# porcupine4v1_10.net
KiCad netlist of a schematic drawn in EAGLE
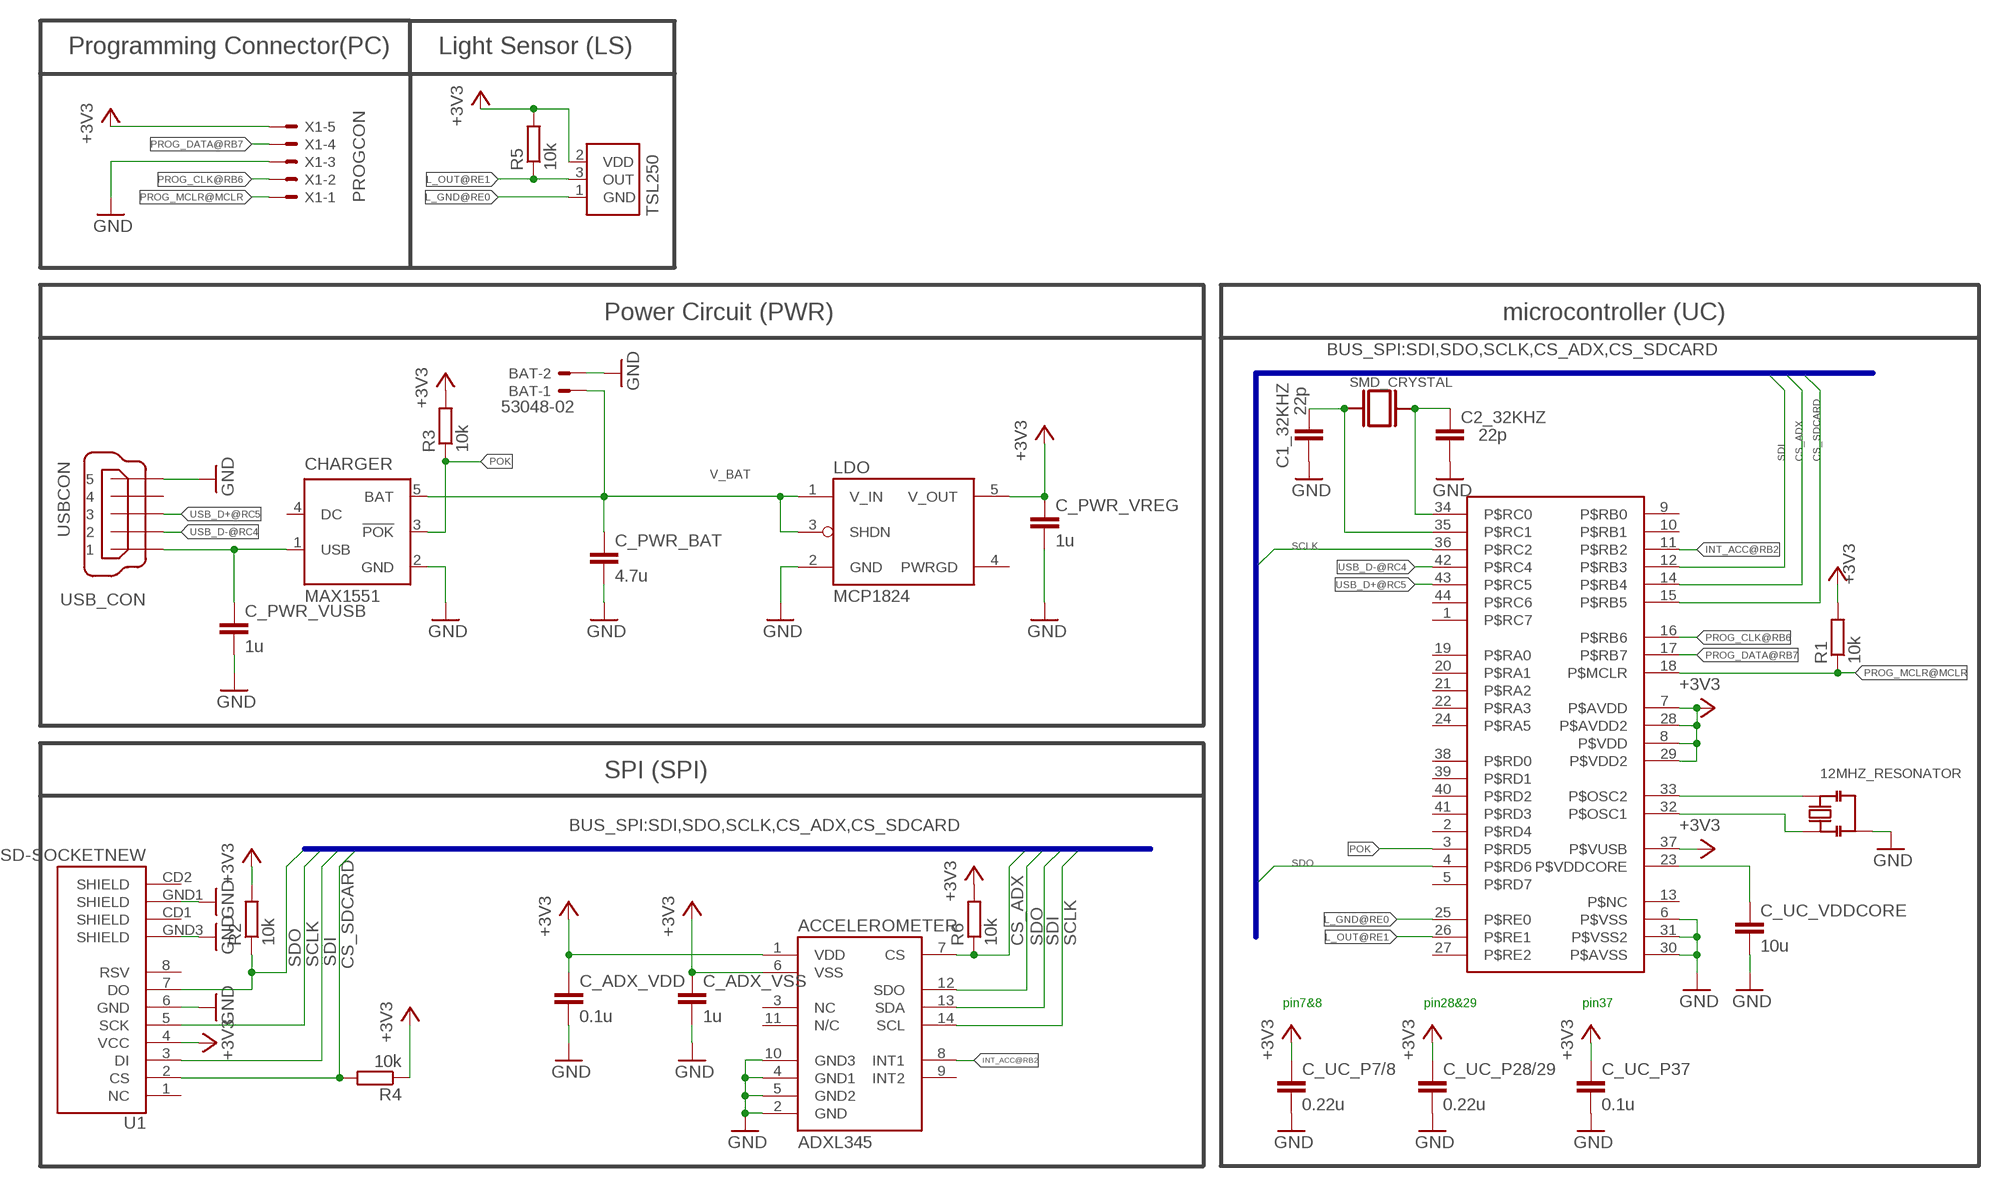
[diagram p0: schematic, sheet 1]

(export (version "E")
  (design (tool "Eeschema 10.0.6"))
  (components
    (comp (ref "12MHZ_RESONATOR")
      (value "RESONATORPRQC-C")
      (footprint "eagle-import:PRQC-C")
      (libsource (lib "eagle-import") (part "RESONATORPRQC-C"))
    )
    (comp (ref "32KHZ_CRYSTAL")
      (value "SMD_CRYSTAL")
      (footprint "eagle-import:SMD_CRYSTAL")
      (libsource (lib "eagle-import") (part "SMD_CRYSTAL"))
    )
    (comp (ref "ACCELEROMETER")
      (value "ADXL345")
      (footprint "eagle-import:LGA14")
      (libsource (lib "eagle-import") (part "ADXL345"))
    )
    (comp (ref "BAT")
      (value "53048-02")
      (footprint "eagle-import:53048-02")
      (fields (field (name "MF") "MOLEX") (field (name "MPN") "53048-0210"))
      (libsource (lib "eagle-import") (part "53?-02048"))
    )
    (comp (ref "C1_32KHZ")
      (value "22p")
      (footprint "eagle-import:C0603K")
      (libsource (lib "eagle-import") (part "C-EUC0603K"))
    )
    (comp (ref "C2_32KHZ")
      (value "22p")
      (footprint "eagle-import:C0603K")
      (libsource (lib "eagle-import") (part "C-EUC0603K"))
    )
    (comp (ref "CHARGER")
      (value "MAX1551")
      (footprint "eagle-import:SOT23-5L")
      (fields (field (name "MF") "MAXIM") (field (name "MPN") "MAX1551EZK-T"))
      (libsource (lib "eagle-import") (part "MAX1551"))
    )
    (comp (ref "C_ADX_VDD")
      (value "0.1u")
      (footprint "eagle-import:C0603K")
      (libsource (lib "eagle-import") (part "C-EUC0603K"))
    )
    (comp (ref "C_ADX_VSS")
      (value "1u")
      (footprint "eagle-import:C0603K")
      (libsource (lib "eagle-import") (part "C-EUC0603K"))
    )
    (comp (ref "C_PWR_BAT")
      (value "4.7u")
      (footprint "eagle-import:C0603K")
      (libsource (lib "eagle-import") (part "C-EUC0603K"))
    )
    (comp (ref "C_PWR_VREG")
      (value "1u")
      (footprint "eagle-import:C0603K")
      (libsource (lib "eagle-import") (part "C-EUC0603K"))
    )
    (comp (ref "C_PWR_VUSB")
      (value "1u")
      (footprint "eagle-import:C0603K")
      (libsource (lib "eagle-import") (part "C-EUC0603K"))
    )
    (comp (ref "C_UC_P7/8")
      (value "0.22u")
      (footprint "eagle-import:C0603K")
      (libsource (lib "eagle-import") (part "C-EUC0603K"))
    )
    (comp (ref "C_UC_P28/29")
      (value "0.22u")
      (footprint "eagle-import:C0603K")
      (libsource (lib "eagle-import") (part "C-EUC0603K"))
    )
    (comp (ref "C_UC_P37")
      (value "0.1u")
      (footprint "eagle-import:C0603K")
      (libsource (lib "eagle-import") (part "C-EUC0603K"))
    )
    (comp (ref "C_UC_VDDCORE")
      (value "10u")
      (footprint "eagle-import:C0805K")
      (libsource (lib "eagle-import") (part "C-EUC0805K"))
    )
    (comp (ref "LDO")
      (value "MCP1824")
      (footprint "eagle-import:SOT-23-5")
      (libsource (lib "eagle-import") (part "MCP1824"))
    )
    (comp (ref "LIGHTSENSE")
      (value "TSL250")
      (footprint "eagle-import:TSL")
      (libsource (lib "eagle-import") (part "TSL250"))
    )
    (comp (ref "PIC_CONTROLLER")
      (value "PIC_P2V6")
      (footprint "eagle-import:QFN44ML8X8")
      (libsource (lib "eagle-import") (part "PIC_P2V6"))
    )
    (comp (ref "R1")
      (value "10k")
      (footprint "eagle-import:R0603")
      (libsource (lib "eagle-import") (part "R-EU_R0603"))
    )
    (comp (ref "R2")
      (value "10k")
      (footprint "eagle-import:R0603")
      (libsource (lib "eagle-import") (part "R-EU_R0603"))
    )
    (comp (ref "R3")
      (value "10k")
      (footprint "eagle-import:R0603")
      (libsource (lib "eagle-import") (part "R-EU_R0603"))
    )
    (comp (ref "R4")
      (value "10k")
      (footprint "eagle-import:R0603")
      (libsource (lib "eagle-import") (part "R-EU_R0603"))
    )
    (comp (ref "R5")
      (value "10k")
      (footprint "eagle-import:R0603")
      (libsource (lib "eagle-import") (part "R-EU_R0603"))
    )
    (comp (ref "R6")
      (value "10k")
      (footprint "eagle-import:R0603")
      (libsource (lib "eagle-import") (part "R-EU_R0603"))
    )
    (comp (ref "U1")
      (value "USD-SOCKETNEW")
      (footprint "eagle-import:MICRO-SD-SOCKET-PP")
      (libsource (lib "eagle-import") (part "USD-SOCKETNEW"))
    )
    (comp (ref "USB_CON")
      (value "USBCON")
      (footprint "eagle-import:248601")
      (libsource (lib "eagle-import") (part "USBCON"))
    )
    (comp (ref "X1")
      (value "PROGCON")
      (footprint "eagle-import:53047-05-OCT")
      (libsource (lib "eagle-import") (part "PROGCON"))
    )
  )
  (nets
    (net (code "2") (name "+3V3") (class "Default")
      (node (ref "ACCELEROMETER") (pin "1") (pinfunction "VDD_1") (pintype "bidirectional"))
      (node (ref "ACCELEROMETER") (pin "6") (pinfunction "VSS_6") (pintype "bidirectional"))
      (node (ref "C_ADX_VDD") (pin "1") (pinfunction "1_1") (pintype "passive"))
      (node (ref "C_ADX_VSS") (pin "1") (pinfunction "1_1") (pintype "passive"))
      (node (ref "C_PWR_VREG") (pin "1") (pinfunction "1_1") (pintype "passive"))
      (node (ref "C_UC_P28/29") (pin "1") (pinfunction "1_1") (pintype "passive"))
      (node (ref "C_UC_P37") (pin "1") (pinfunction "1_1") (pintype "passive"))
      (node (ref "C_UC_P7/8") (pin "1") (pinfunction "1_1") (pintype "passive"))
      (node (ref "LDO") (pin "5") (pinfunction "V_OUT_5") (pintype "bidirectional"))
      (node (ref "LIGHTSENSE") (pin "2") (pinfunction "VDD_2") (pintype "power_in"))
      (node (ref "PIC_CONTROLLER") (pin "28") (pinfunction "P$AVDD2_28") (pintype "bidirectional"))
      (node (ref "PIC_CONTROLLER") (pin "29") (pinfunction "P$VDD2_29") (pintype "bidirectional"))
      (node (ref "PIC_CONTROLLER") (pin "37") (pinfunction "P$VUSB_37") (pintype "bidirectional"))
      (node (ref "PIC_CONTROLLER") (pin "7") (pinfunction "P$AVDD_7") (pintype "input"))
      (node (ref "PIC_CONTROLLER") (pin "8") (pinfunction "P$VDD_8") (pintype "bidirectional"))
      (node (ref "R1") (pin "2") (pinfunction "2_2") (pintype "passive"))
      (node (ref "R2") (pin "2") (pinfunction "2_2") (pintype "passive"))
      (node (ref "R3") (pin "2") (pinfunction "2_2") (pintype "passive"))
      (node (ref "R4") (pin "1") (pinfunction "1_1") (pintype "passive"))
      (node (ref "R5") (pin "2") (pinfunction "2_2") (pintype "passive"))
      (node (ref "R6") (pin "2") (pinfunction "2_2") (pintype "passive"))
      (node (ref "U1") (pin "4") (pinfunction "VCC_4") (pintype "bidirectional"))
      (node (ref "X1") (pin "5") (pinfunction "S_5") (pintype "passive"))
    )
    (net (code "3") (name "/CS_ADX") (class "Default")
      (node (ref "ACCELEROMETER") (pin "7") (pinfunction "CS_7") (pintype "bidirectional"))
      (node (ref "PIC_CONTROLLER") (pin "14") (pinfunction "P$RB4_14") (pintype "bidirectional"))
      (node (ref "R6") (pin "1") (pinfunction "1_1") (pintype "passive"))
    )
    (net (code "4") (name "/CS_SDCARD") (class "Default")
      (node (ref "PIC_CONTROLLER") (pin "15") (pinfunction "P$RB5_15") (pintype "bidirectional"))
      (node (ref "R4") (pin "2") (pinfunction "2_2") (pintype "passive"))
      (node (ref "U1") (pin "2") (pinfunction "CS_2") (pintype "bidirectional"))
    )
    (net (code "5") (name "/P$RD7") (class "Default")
      (node (ref "PIC_CONTROLLER") (pin "5") (pinfunction "P$RD7_5") (pintype "power_in"))
    )
    (net (code "6") (name "/SCLK") (class "Default")
      (node (ref "ACCELEROMETER") (pin "14") (pinfunction "SCL_14") (pintype "bidirectional"))
      (node (ref "PIC_CONTROLLER") (pin "36") (pinfunction "P$RC2_36") (pintype "bidirectional"))
      (node (ref "U1") (pin "5") (pinfunction "SCK_5") (pintype "bidirectional"))
    )
    (net (code "7") (name "/SDI") (class "Default")
      (node (ref "ACCELEROMETER") (pin "13") (pinfunction "SDA_13") (pintype "bidirectional"))
      (node (ref "PIC_CONTROLLER") (pin "12") (pinfunction "P$RB3_12") (pintype "bidirectional"))
      (node (ref "U1") (pin "3") (pinfunction "DI_3") (pintype "bidirectional"))
    )
    (net (code "8") (name "/SDO") (class "Default")
      (node (ref "ACCELEROMETER") (pin "12") (pinfunction "SDO_12") (pintype "bidirectional"))
      (node (ref "PIC_CONTROLLER") (pin "4") (pinfunction "P$RD6_4") (pintype "bidirectional"))
      (node (ref "R2") (pin "1") (pinfunction "1_1") (pintype "passive"))
      (node (ref "U1") (pin "7") (pinfunction "DO_7") (pintype "bidirectional"))
    )
    (net (code "9") (name "/V_BAT") (class "Default")
      (node (ref "BAT") (pin "1") (pinfunction "S_1") (pintype "passive"))
      (node (ref "CHARGER") (pin "5") (pinfunction "BAT_5") (pintype "passive"))
      (node (ref "C_PWR_BAT") (pin "1") (pinfunction "1_1") (pintype "passive"))
      (node (ref "LDO") (pin "1") (pinfunction "V_IN_1") (pintype "bidirectional"))
      (node (ref "LDO") (pin "3") (pinfunction "SHDN_3") (pintype "bidirectional"))
    )
    (net (code "11") (name "GND") (class "Default")
      (node (ref "12MHZ_RESONATOR") (pin "2_GND") (pinfunction "GND_2_GND") (pintype "bidirectional"))
      (node (ref "ACCELEROMETER") (pin "10") (pinfunction "GND3_10") (pintype "bidirectional"))
      (node (ref "ACCELEROMETER") (pin "2") (pinfunction "GND_2") (pintype "bidirectional"))
      (node (ref "ACCELEROMETER") (pin "4") (pinfunction "GND1_4") (pintype "bidirectional"))
      (node (ref "ACCELEROMETER") (pin "5") (pinfunction "GND2_5") (pintype "bidirectional"))
      (node (ref "BAT") (pin "2") (pinfunction "S_2") (pintype "passive"))
      (node (ref "C1_32KHZ") (pin "2") (pinfunction "2_2") (pintype "passive"))
      (node (ref "C2_32KHZ") (pin "2") (pinfunction "2_2") (pintype "passive"))
      (node (ref "CHARGER") (pin "2") (pinfunction "GND_2") (pintype "power_in"))
      (node (ref "C_ADX_VDD") (pin "2") (pinfunction "2_2") (pintype "passive"))
      (node (ref "C_ADX_VSS") (pin "2") (pinfunction "2_2") (pintype "passive"))
      (node (ref "C_PWR_BAT") (pin "2") (pinfunction "2_2") (pintype "passive"))
      (node (ref "C_PWR_VREG") (pin "2") (pinfunction "2_2") (pintype "passive"))
      (node (ref "C_PWR_VUSB") (pin "2") (pinfunction "2_2") (pintype "passive"))
      (node (ref "C_UC_P28/29") (pin "2") (pinfunction "2_2") (pintype "passive"))
      (node (ref "C_UC_P37") (pin "2") (pinfunction "2_2") (pintype "passive"))
      (node (ref "C_UC_P7/8") (pin "2") (pinfunction "2_2") (pintype "passive"))
      (node (ref "C_UC_VDDCORE") (pin "2") (pinfunction "2_2") (pintype "passive"))
      (node (ref "LDO") (pin "2") (pinfunction "GND_2") (pintype "bidirectional"))
      (node (ref "PIC_CONTROLLER") (pin "30") (pinfunction "P$AVSS_30") (pintype "input"))
      (node (ref "PIC_CONTROLLER") (pin "31") (pinfunction "P$VSS2_31") (pintype "output"))
      (node (ref "PIC_CONTROLLER") (pin "6") (pinfunction "P$VSS_6") (pintype "input"))
      (node (ref "U1") (pin "6") (pinfunction "GND_6") (pintype "bidirectional"))
      (node (ref "U1") (pin "GND1") (pinfunction "SHIELD_GND1") (pintype "bidirectional"))
      (node (ref "U1") (pin "GND3") (pinfunction "SHIELD_GND3") (pintype "bidirectional"))
      (node (ref "USB_CON") (pin "5") (pinfunction "5_5") (pintype "input"))
      (node (ref "X1") (pin "3") (pinfunction "S_3") (pintype "passive"))
    )
    (net (code "12") (name "INT_ACC@RB2") (class "Default")
      (node (ref "ACCELEROMETER") (pin "8") (pinfunction "INT1_8") (pintype "bidirectional"))
      (node (ref "PIC_CONTROLLER") (pin "11") (pinfunction "P$RB2_11") (pintype "power_in"))
    )
    (net (code "13") (name "L_GND@RE0") (class "Default")
      (node (ref "LIGHTSENSE") (pin "1") (pinfunction "GND_1") (pintype "power_in"))
      (node (ref "PIC_CONTROLLER") (pin "25") (pinfunction "P$RE0_25") (pintype "bidirectional"))
    )
    (net (code "14") (name "L_OUT@RE1") (class "Default")
      (node (ref "LIGHTSENSE") (pin "3") (pinfunction "OUT_3") (pintype "output"))
      (node (ref "PIC_CONTROLLER") (pin "26") (pinfunction "P$RE1_26") (pintype "input"))
      (node (ref "R5") (pin "1") (pinfunction "1_1") (pintype "passive"))
    )
    (net (code "15") (name "Net-(12MHZ_RESONATOR-2)") (class "Default")
      (node (ref "12MHZ_RESONATOR") (pin "3") (pinfunction "2_3") (pintype "bidirectional"))
      (node (ref "PIC_CONTROLLER") (pin "32") (pinfunction "P$OSC1_32") (pintype "bidirectional"))
    )
    (net (code "16") (name "Net-(32KHZ_CRYSTAL-1)") (class "Default")
      (node (ref "32KHZ_CRYSTAL") (pin "P$1") (pinfunction "1_P$1") (pintype "passive"))
      (node (ref "C1_32KHZ") (pin "1") (pinfunction "1_1") (pintype "passive"))
      (node (ref "PIC_CONTROLLER") (pin "35") (pinfunction "P$RC1_35") (pintype "bidirectional"))
    )
    (net (code "17") (name "Net-(32KHZ_CRYSTAL-2)") (class "Default")
      (node (ref "32KHZ_CRYSTAL") (pin "P$2") (pinfunction "2_P$2") (pintype "passive"))
      (node (ref "C2_32KHZ") (pin "1") (pinfunction "1_1") (pintype "passive"))
      (node (ref "PIC_CONTROLLER") (pin "34") (pinfunction "P$RC0_34") (pintype "bidirectional"))
    )
    (net (code "18") (name "Net-(CHARGER-USB)") (class "Default")
      (node (ref "CHARGER") (pin "1") (pinfunction "USB_1") (pintype "input"))
      (node (ref "C_PWR_VUSB") (pin "1") (pinfunction "1_1") (pintype "passive"))
      (node (ref "USB_CON") (pin "1") (pinfunction "1_1") (pintype "input"))
    )
    (net (code "19") (name "Net-(PIC_CONTROLLER-P$OSC2)") (class "Default")
      (node (ref "12MHZ_RESONATOR") (pin "1") (pinfunction "1_1") (pintype "bidirectional"))
      (node (ref "PIC_CONTROLLER") (pin "33") (pinfunction "P$OSC2_33") (pintype "bidirectional"))
    )
    (net (code "20") (name "Net-(PIC_CONTROLLER-P$VDDCORE)") (class "Default")
      (node (ref "C_UC_VDDCORE") (pin "1") (pinfunction "1_1") (pintype "passive"))
      (node (ref "PIC_CONTROLLER") (pin "23") (pinfunction "P$VDDCORE_23") (pintype "bidirectional"))
    )
    (net (code "21") (name "POK") (class "Default")
      (node (ref "CHARGER") (pin "3") (pinfunction "~{POK}_3") (pintype "output"))
      (node (ref "PIC_CONTROLLER") (pin "3") (pinfunction "P$RD5_3") (pintype "power_in"))
      (node (ref "R3") (pin "1") (pinfunction "1_1") (pintype "passive"))
    )
    (net (code "22") (name "PROG_CLK@RB6") (class "Default")
      (node (ref "PIC_CONTROLLER") (pin "16") (pinfunction "P$RB6_16") (pintype "power_in"))
      (node (ref "X1") (pin "2") (pinfunction "S_2") (pintype "passive"))
    )
    (net (code "23") (name "PROG_DATA@RB7") (class "Default")
      (node (ref "PIC_CONTROLLER") (pin "17") (pinfunction "P$RB7_17") (pintype "power_in"))
      (node (ref "X1") (pin "4") (pinfunction "S_4") (pintype "passive"))
    )
    (net (code "24") (name "PROG_MCLR@MCLR") (class "Default")
      (node (ref "PIC_CONTROLLER") (pin "18") (pinfunction "P$MCLR_18") (pintype "input"))
      (node (ref "R1") (pin "1") (pinfunction "1_1") (pintype "passive"))
      (node (ref "X1") (pin "1") (pinfunction "S_1") (pintype "passive"))
    )
    (net (code "25") (name "USB_D+@RC5") (class "Default")
      (node (ref "PIC_CONTROLLER") (pin "43") (pinfunction "P$RC5_43") (pintype "bidirectional"))
      (node (ref "USB_CON") (pin "3") (pinfunction "3_3") (pintype "input"))
    )
    (net (code "26") (name "USB_D-@RC4") (class "Default")
      (node (ref "PIC_CONTROLLER") (pin "42") (pinfunction "P$RC4_42") (pintype "bidirectional"))
      (node (ref "USB_CON") (pin "2") (pinfunction "2_2") (pintype "input"))
    )
    (net (code "27") (name "unconnected-(ACCELEROMETER-INT2-Pad9)") (class "Default")
      (node (ref "ACCELEROMETER") (pin "9") (pinfunction "INT2_9") (pintype "bidirectional"))
    )
    (net (code "28") (name "unconnected-(ACCELEROMETER-NC-Pad3)") (class "Default")
      (node (ref "ACCELEROMETER") (pin "3") (pinfunction "NC_3") (pintype "bidirectional"))
    )
    (net (code "29") (name "unconnected-(ACCELEROMETER-N{slash}C-Pad11)") (class "Default")
      (node (ref "ACCELEROMETER") (pin "11") (pinfunction "N/C_11") (pintype "bidirectional"))
    )
    (net (code "30") (name "unconnected-(CHARGER-DC-Pad4)") (class "Default")
      (node (ref "CHARGER") (pin "4") (pinfunction "DC_4") (pintype "input"))
    )
    (net (code "31") (name "unconnected-(LDO-PWRGD-Pad4)") (class "Default")
      (node (ref "LDO") (pin "4") (pinfunction "PWRGD_4") (pintype "bidirectional"))
    )
    (net (code "32") (name "unconnected-(PIC_CONTROLLER-P$NC-Pad13)") (class "Default")
      (node (ref "PIC_CONTROLLER") (pin "13") (pinfunction "P$NC_13") (pintype "bidirectional"))
    )
    (net (code "33") (name "unconnected-(PIC_CONTROLLER-P$RA0-Pad19)") (class "Default")
      (node (ref "PIC_CONTROLLER") (pin "19") (pinfunction "P$RA0_19") (pintype "bidirectional"))
    )
    (net (code "34") (name "unconnected-(PIC_CONTROLLER-P$RA1-Pad20)") (class "Default")
      (node (ref "PIC_CONTROLLER") (pin "20") (pinfunction "P$RA1_20") (pintype "bidirectional"))
    )
    (net (code "35") (name "unconnected-(PIC_CONTROLLER-P$RA2-Pad21)") (class "Default")
      (node (ref "PIC_CONTROLLER") (pin "21") (pinfunction "P$RA2_21") (pintype "bidirectional"))
    )
    (net (code "36") (name "unconnected-(PIC_CONTROLLER-P$RA3-Pad22)") (class "Default")
      (node (ref "PIC_CONTROLLER") (pin "22") (pinfunction "P$RA3_22") (pintype "bidirectional"))
    )
    (net (code "37") (name "unconnected-(PIC_CONTROLLER-P$RA5-Pad24)") (class "Default")
      (node (ref "PIC_CONTROLLER") (pin "24") (pinfunction "P$RA5_24") (pintype "bidirectional"))
    )
    (net (code "38") (name "unconnected-(PIC_CONTROLLER-P$RB0-Pad9)") (class "Default")
      (node (ref "PIC_CONTROLLER") (pin "9") (pinfunction "P$RB0_9") (pintype "bidirectional"))
    )
    (net (code "39") (name "unconnected-(PIC_CONTROLLER-P$RB1-Pad10)") (class "Default")
      (node (ref "PIC_CONTROLLER") (pin "10") (pinfunction "P$RB1_10") (pintype "bidirectional"))
    )
    (net (code "40") (name "unconnected-(PIC_CONTROLLER-P$RC6-Pad44)") (class "Default")
      (node (ref "PIC_CONTROLLER") (pin "44") (pinfunction "P$RC6_44") (pintype "bidirectional"))
    )
    (net (code "41") (name "unconnected-(PIC_CONTROLLER-P$RC7-Pad1)") (class "Default")
      (node (ref "PIC_CONTROLLER") (pin "1") (pinfunction "P$RC7_1") (pintype "bidirectional"))
    )
    (net (code "42") (name "unconnected-(PIC_CONTROLLER-P$RD0-Pad38)") (class "Default")
      (node (ref "PIC_CONTROLLER") (pin "38") (pinfunction "P$RD0_38") (pintype "bidirectional"))
    )
    (net (code "43") (name "unconnected-(PIC_CONTROLLER-P$RD1-Pad39)") (class "Default")
      (node (ref "PIC_CONTROLLER") (pin "39") (pinfunction "P$RD1_39") (pintype "bidirectional"))
    )
    (net (code "44") (name "unconnected-(PIC_CONTROLLER-P$RD2-Pad40)") (class "Default")
      (node (ref "PIC_CONTROLLER") (pin "40") (pinfunction "P$RD2_40") (pintype "bidirectional"))
    )
    (net (code "45") (name "unconnected-(PIC_CONTROLLER-P$RD3-Pad41)") (class "Default")
      (node (ref "PIC_CONTROLLER") (pin "41") (pinfunction "P$RD3_41") (pintype "bidirectional"))
    )
    (net (code "46") (name "unconnected-(PIC_CONTROLLER-P$RD4-Pad2)") (class "Default")
      (node (ref "PIC_CONTROLLER") (pin "2") (pinfunction "P$RD4_2") (pintype "bidirectional"))
    )
    (net (code "47") (name "unconnected-(PIC_CONTROLLER-P$RE2-Pad27)") (class "Default")
      (node (ref "PIC_CONTROLLER") (pin "27") (pinfunction "P$RE2_27") (pintype "bidirectional"))
    )
    (net (code "48") (name "unconnected-(U1-NC-Pad1)") (class "Default")
      (node (ref "U1") (pin "1") (pinfunction "NC_1") (pintype "bidirectional"))
    )
    (net (code "49") (name "unconnected-(U1-RSV-Pad8)") (class "Default")
      (node (ref "U1") (pin "8") (pinfunction "RSV_8") (pintype "bidirectional"))
    )
    (net (code "50") (name "unconnected-(U1-SHIELD-PadCD1)") (class "Default")
      (node (ref "U1") (pin "CD1") (pinfunction "SHIELD_CD1") (pintype "bidirectional"))
    )
    (net (code "51") (name "unconnected-(U1-SHIELD-PadCD2)") (class "Default")
      (node (ref "U1") (pin "CD2") (pinfunction "SHIELD_CD2") (pintype "bidirectional"))
    )
    (net (code "52") (name "unconnected-(USB_CON-Pad4)") (class "Default")
      (node (ref "USB_CON") (pin "4") (pinfunction "4_4") (pintype "input"))
    )
  )
)
